# Raspberry.net
KiCad netlist of a schematic drawn in Altium Designer
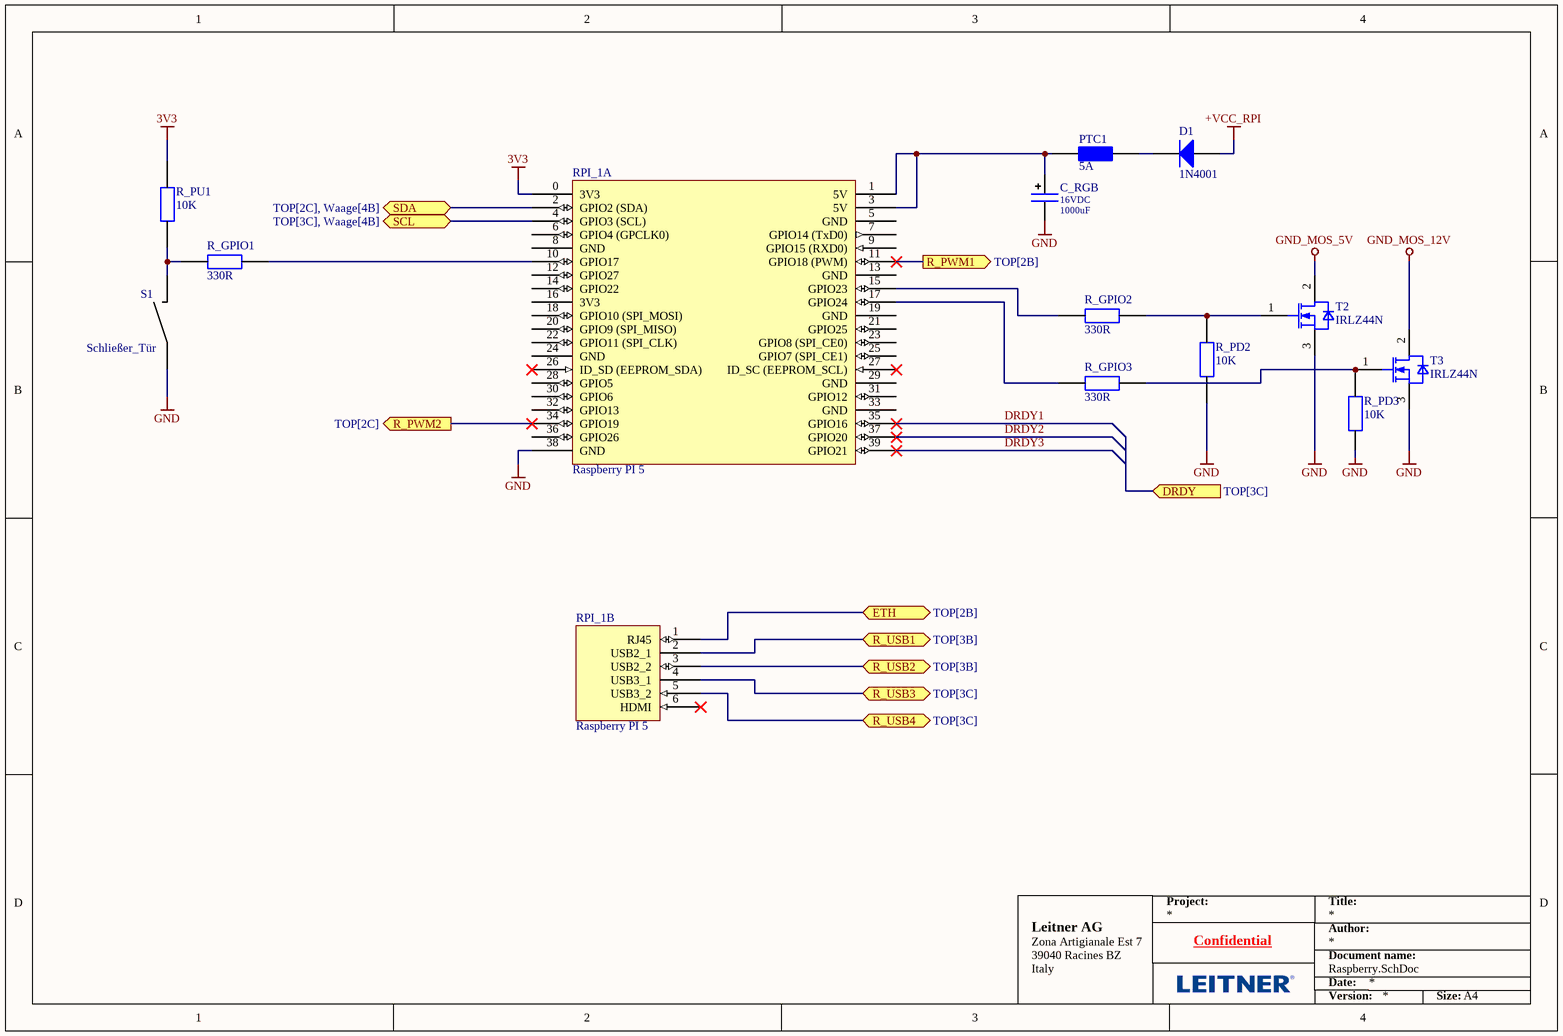
[diagram p0: Raspberry.SchDoc]

(export (version "E")
  (design (tool "Eeschema 10.0.6"))
  (components
    (comp (ref "C_RGB")
      (value "1000uF")
      (fields (field (name "SPANNUNG") "16VDC") (field (name "LADUNG") "1000uF"))
      (libsource (lib "3D_Scanner") (part "Elko 1000uF"))
    )
    (comp (ref "D1")
      (value "1N4001")
      (footprint "D_DO41-RM4")
      (description "Si-Diode; 50V, 1.00A, 3.00us (Diodes, Inc.)")
      (libsource (lib "HTLinn_D") (part "1N4001"))
    )
    (comp (ref "PTC1")
      (value "5A")
      (fields (field (name "CURRENT") "5A"))
      (libsource (lib "3D_Scanner") (part "PTC 5A"))
    )
    (comp (ref "RPI_1") (value "Raspberry PI 5") (libsource (lib "3D_Scanner") (part "Raspberry PI")))
    (comp (ref "R_GPIO1")
      (value "330R")
      (fields (field (name "WIDERSTAND") "330R"))
      (libsource (lib "3D_Scanner") (part "R 330"))
    )
    (comp (ref "R_GPIO2")
      (value "330R")
      (fields (field (name "WIDERSTAND") "330R"))
      (libsource (lib "3D_Scanner") (part "R 330"))
    )
    (comp (ref "R_GPIO3")
      (value "330R")
      (fields (field (name "WIDERSTAND") "330R"))
      (libsource (lib "3D_Scanner") (part "R 330"))
    )
    (comp (ref "R_PD2")
      (value "10K")
      (fields (field (name "WIDERSTAND") "10K"))
      (libsource (lib "3D_Scanner") (part "R 10K"))
    )
    (comp (ref "R_PD3")
      (value "10K")
      (fields (field (name "WIDERSTAND") "10K"))
      (libsource (lib "3D_Scanner") (part "R 10K"))
    )
    (comp (ref "R_PU1")
      (value "10K")
      (fields (field (name "WIDERSTAND") "10K"))
      (libsource (lib "3D_Scanner") (part "R 10K"))
    )
    (comp (ref "S1") (value "Schließer_Tür") (libsource (lib "3D_Scanner") (part "S_Schließer")))
    (comp (ref "T2")
      (value "IRLZ44N")
      (description "OptiMOS 3 Power-Transistor, VDS 100V")
      (fields (field (name "MANUFACTURER") "Infineon Technologies"))
      (libsource (lib "IRLZ44N") (part "IRLZ44N"))
    )
    (comp (ref "T3")
      (value "IRLZ44N")
      (description "OptiMOS 3 Power-Transistor, VDS 100V")
      (fields (field (name "MANUFACTURER") "Infineon Technologies"))
      (libsource (lib "IRLZ44N") (part "IRLZ44N"))
    )
  )
  (nets
    (net (code "1") (name "+VCC_RPI") (class "Default")
      (node (ref "D1") (pin "A") (pinfunction "A_A") (pintype "passive"))
    )
    (net (code "3") (name "/DRDY1") (class "Default")
      (node (ref "RPI_1") (pin "35") (pinfunction "GPIO16_35") (pintype "bidirectional+no_connect"))
    )
    (net (code "4") (name "/DRDY2") (class "Default")
      (node (ref "RPI_1") (pin "37") (pinfunction "GPIO20_37") (pintype "bidirectional+no_connect"))
    )
    (net (code "5") (name "/DRDY3") (class "Default")
      (node (ref "RPI_1") (pin "39") (pinfunction "GPIO21_39") (pintype "bidirectional+no_connect"))
    )
    (net (code "6") (name "/ETH") (class "Default")
      (node (ref "RPI_1") (pin "1") (pinfunction "RJ45_1") (pintype "bidirectional"))
    )
    (net (code "7") (name "/R_PWM1") (class "Default")
      (node (ref "RPI_1") (pin "11") (pinfunction "GPIO18_(PWM)_11") (pintype "bidirectional+no_connect"))
    )
    (net (code "8") (name "/R_PWM2") (class "Default")
      (node (ref "RPI_1") (pin "34") (pinfunction "GPIO19_34") (pintype "bidirectional+no_connect"))
    )
    (net (code "9") (name "/R_USB1") (class "Default")
      (node (ref "RPI_1") (pin "2") (pinfunction "USB2_1_2") (pintype "power_in"))
    )
    (net (code "10") (name "/R_USB2") (class "Default")
      (node (ref "RPI_1") (pin "3") (pinfunction "USB2_2_3") (pintype "bidirectional"))
    )
    (net (code "11") (name "/R_USB3") (class "Default")
      (node (ref "RPI_1") (pin "4") (pinfunction "USB3_1_4") (pintype "power_in"))
    )
    (net (code "12") (name "/R_USB4") (class "Default")
      (node (ref "RPI_1") (pin "5") (pinfunction "USB3_2_5") (pintype "input"))
    )
    (net (code "13") (name "/SCL") (class "Default")
      (node (ref "RPI_1") (pin "4") (pinfunction "GPIO3_(SCL)_4") (pintype "bidirectional"))
    )
    (net (code "14") (name "/SDA") (class "Default")
      (node (ref "RPI_1") (pin "2") (pinfunction "GPIO2_(SDA)_2") (pintype "bidirectional"))
    )
    (net (code "15") (name "3V3") (class "Default")
      (node (ref "RPI_1") (pin "0") (pinfunction "3V3_0") (pintype "power_in"))
      (node (ref "R_PU1") (pin "1") (pinfunction "1_1") (pintype "passive"))
    )
    (net (code "16") (name "GND") (class "Default")
      (node (ref "C_RGB") (pin "0") (pinfunction "0_0") (pintype "passive"))
      (node (ref "RPI_1") (pin "38") (pinfunction "GND_38") (pintype "power_in"))
      (node (ref "R_PD2") (pin "0") (pinfunction "0_0") (pintype "passive"))
      (node (ref "R_PD3") (pin "0") (pinfunction "0_0") (pintype "passive"))
      (node (ref "T2") (pin "3") (pinfunction "SOURCE_3") (pintype "passive"))
      (node (ref "T3") (pin "3") (pinfunction "SOURCE_3") (pintype "passive"))
    )
    (net (code "17") (name "GND_MOS_5V") (class "Default")
      (node (ref "T2") (pin "2") (pinfunction "DRAIN_2") (pintype "passive"))
    )
    (net (code "18") (name "GND_MOS_12V") (class "Default")
      (node (ref "T3") (pin "2") (pinfunction "DRAIN_2") (pintype "passive"))
    )
    (net (code "19") (name "Net-(C_RGB-Pad1)") (class "Default")
      (node (ref "C_RGB") (pin "1") (pinfunction "1_1") (pintype "passive"))
      (node (ref "PTC1") (pin "0") (pinfunction "0_0") (pintype "passive"))
      (node (ref "RPI_1") (pin "1") (pinfunction "5V_1") (pintype "power_in"))
      (node (ref "RPI_1") (pin "3") (pinfunction "5V_3") (pintype "power_in"))
    )
    (net (code "20") (name "Net-(D1-K)") (class "Default")
      (node (ref "D1") (pin "C") (pinfunction "K_C") (pintype "passive"))
      (node (ref "PTC1") (pin "1") (pinfunction "1_1") (pintype "passive"))
    )
    (net (code "21") (name "Net-(RPI_1A-GPIO17)") (class "Default")
      (node (ref "RPI_1") (pin "10") (pinfunction "GPIO17_10") (pintype "bidirectional"))
      (node (ref "R_GPIO1") (pin "1") (pinfunction "1_1") (pintype "passive"))
    )
    (net (code "22") (name "Net-(RPI_1A-GPIO23)") (class "Default")
      (node (ref "RPI_1") (pin "15") (pinfunction "GPIO23_15") (pintype "bidirectional"))
      (node (ref "R_GPIO2") (pin "0") (pinfunction "0_0") (pintype "passive"))
    )
    (net (code "23") (name "Net-(RPI_1A-GPIO24)") (class "Default")
      (node (ref "RPI_1") (pin "17") (pinfunction "GPIO24_17") (pintype "bidirectional"))
      (node (ref "R_GPIO3") (pin "0") (pinfunction "0_0") (pintype "passive"))
    )
    (net (code "24") (name "Net-(R_GPIO1-Pad0)") (class "Default")
      (node (ref "R_GPIO1") (pin "0") (pinfunction "0_0") (pintype "passive"))
      (node (ref "R_PU1") (pin "0") (pinfunction "0_0") (pintype "passive"))
    )
    (net (code "25") (name "Net-(T2-GATE)") (class "Default")
      (node (ref "R_GPIO2") (pin "1") (pinfunction "1_1") (pintype "passive"))
      (node (ref "R_PD2") (pin "1") (pinfunction "1_1") (pintype "passive"))
      (node (ref "T2") (pin "1") (pinfunction "GATE_1") (pintype "passive"))
    )
    (net (code "26") (name "Net-(T3-GATE)") (class "Default")
      (node (ref "R_GPIO3") (pin "1") (pinfunction "1_1") (pintype "passive"))
      (node (ref "R_PD3") (pin "1") (pinfunction "1_1") (pintype "passive"))
      (node (ref "T3") (pin "1") (pinfunction "GATE_1") (pintype "passive"))
    )
    (net (code "27") (name "unconnected-(RPI_1A-3V3-Pad16)") (class "Default")
      (node (ref "RPI_1") (pin "16") (pinfunction "3V3_16") (pintype "power_in"))
    )
    (net (code "28") (name "unconnected-(RPI_1A-GND-Pad5)") (class "Default")
      (node (ref "RPI_1") (pin "5") (pinfunction "GND_5") (pintype "power_in"))
    )
    (net (code "29") (name "unconnected-(RPI_1A-GND-Pad8)") (class "Default")
      (node (ref "RPI_1") (pin "8") (pinfunction "GND_8") (pintype "power_in"))
    )
    (net (code "30") (name "unconnected-(RPI_1A-GND-Pad13)") (class "Default")
      (node (ref "RPI_1") (pin "13") (pinfunction "GND_13") (pintype "power_in"))
    )
    (net (code "31") (name "unconnected-(RPI_1A-GND-Pad19)") (class "Default")
      (node (ref "RPI_1") (pin "19") (pinfunction "GND_19") (pintype "power_in"))
    )
    (net (code "32") (name "unconnected-(RPI_1A-GND-Pad24)") (class "Default")
      (node (ref "RPI_1") (pin "24") (pinfunction "GND_24") (pintype "power_in"))
    )
    (net (code "33") (name "unconnected-(RPI_1A-GND-Pad29)") (class "Default")
      (node (ref "RPI_1") (pin "29") (pinfunction "GND_29") (pintype "power_in"))
    )
    (net (code "34") (name "unconnected-(RPI_1A-GND-Pad33)") (class "Default")
      (node (ref "RPI_1") (pin "33") (pinfunction "GND_33") (pintype "power_in"))
    )
    (net (code "35") (name "unconnected-(RPI_1A-GPIO4_(GPCLK0)-Pad6)") (class "Default")
      (node (ref "RPI_1") (pin "6") (pinfunction "GPIO4_(GPCLK0)_6") (pintype "bidirectional"))
    )
    (net (code "36") (name "unconnected-(RPI_1A-GPIO5-Pad28)") (class "Default")
      (node (ref "RPI_1") (pin "28") (pinfunction "GPIO5_28") (pintype "bidirectional"))
    )
    (net (code "37") (name "unconnected-(RPI_1A-GPIO6-Pad30)") (class "Default")
      (node (ref "RPI_1") (pin "30") (pinfunction "GPIO6_30") (pintype "bidirectional"))
    )
    (net (code "38") (name "unconnected-(RPI_1A-GPIO7_(SPI_CE1)-Pad25)") (class "Default")
      (node (ref "RPI_1") (pin "25") (pinfunction "GPIO7_(SPI_CE1)_25") (pintype "bidirectional"))
    )
    (net (code "39") (name "unconnected-(RPI_1A-GPIO8_(SPI_CE0)-Pad23)") (class "Default")
      (node (ref "RPI_1") (pin "23") (pinfunction "GPIO8_(SPI_CE0)_23") (pintype "bidirectional"))
    )
    (net (code "40") (name "unconnected-(RPI_1A-GPIO9_(SPI_MISO)-Pad20)") (class "Default")
      (node (ref "RPI_1") (pin "20") (pinfunction "GPIO9_(SPI_MISO)_20") (pintype "bidirectional"))
    )
    (net (code "41") (name "unconnected-(RPI_1A-GPIO10_(SPI_MOSI)-Pad18)") (class "Default")
      (node (ref "RPI_1") (pin "18") (pinfunction "GPIO10_(SPI_MOSI)_18") (pintype "bidirectional"))
    )
    (net (code "42") (name "unconnected-(RPI_1A-GPIO11_(SPI_CLK)-Pad22)") (class "Default")
      (node (ref "RPI_1") (pin "22") (pinfunction "GPIO11_(SPI_CLK)_22") (pintype "bidirectional"))
    )
    (net (code "43") (name "unconnected-(RPI_1A-GPIO12-Pad31)") (class "Default")
      (node (ref "RPI_1") (pin "31") (pinfunction "GPIO12_31") (pintype "bidirectional"))
    )
    (net (code "44") (name "unconnected-(RPI_1A-GPIO13-Pad32)") (class "Default")
      (node (ref "RPI_1") (pin "32") (pinfunction "GPIO13_32") (pintype "bidirectional"))
    )
    (net (code "45") (name "unconnected-(RPI_1A-GPIO14_(TxD0)-Pad7)") (class "Default")
      (node (ref "RPI_1") (pin "7") (pinfunction "GPIO14_(TxD0)_7") (pintype "output"))
    )
    (net (code "46") (name "unconnected-(RPI_1A-GPIO15_(RXD0)-Pad9)") (class "Default")
      (node (ref "RPI_1") (pin "9") (pinfunction "GPIO15_(RXD0)_9") (pintype "input"))
    )
    (net (code "47") (name "unconnected-(RPI_1A-GPIO22-Pad14)") (class "Default")
      (node (ref "RPI_1") (pin "14") (pinfunction "GPIO22_14") (pintype "bidirectional"))
    )
    (net (code "48") (name "unconnected-(RPI_1A-GPIO25-Pad21)") (class "Default")
      (node (ref "RPI_1") (pin "21") (pinfunction "GPIO25_21") (pintype "bidirectional"))
    )
    (net (code "49") (name "unconnected-(RPI_1A-GPIO26-Pad36)") (class "Default")
      (node (ref "RPI_1") (pin "36") (pinfunction "GPIO26_36") (pintype "bidirectional"))
    )
    (net (code "50") (name "unconnected-(RPI_1A-GPIO27-Pad12)") (class "Default")
      (node (ref "RPI_1") (pin "12") (pinfunction "GPIO27_12") (pintype "bidirectional"))
    )
    (net (code "51") (name "unconnected-(RPI_1A-ID_SC_(EEPROM_SCL)-Pad27)") (class "Default")
      (node (ref "RPI_1") (pin "27") (pinfunction "ID_SC_(EEPROM_SCL)_27") (pintype "input+no_connect"))
    )
    (net (code "52") (name "unconnected-(RPI_1A-ID_SD_(EEPROM_SDA)-Pad26)") (class "Default")
      (node (ref "RPI_1") (pin "26") (pinfunction "ID_SD_(EEPROM_SDA)_26") (pintype "input+no_connect"))
    )
    (net (code "53") (name "unconnected-(RPI_1B-HDMI-Pad6)") (class "Default")
      (node (ref "RPI_1") (pin "6") (pinfunction "HDMI_6") (pintype "input+no_connect"))
    )
  )
)
